# main.net
KiCad netlist of a schematic drawn in EAGLE
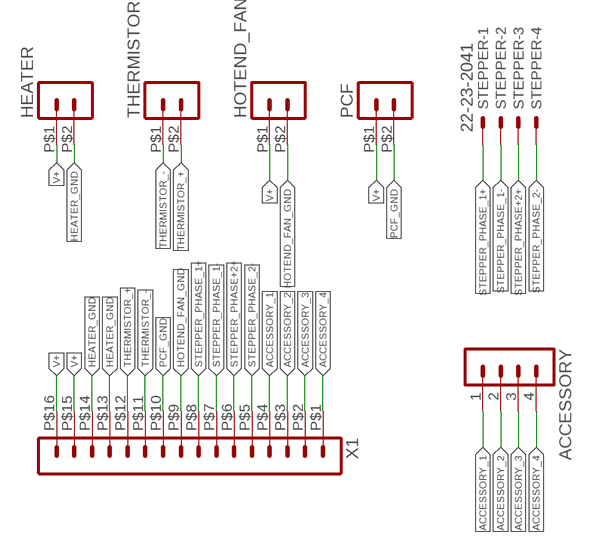
[diagram p0: schematic, sheet 1]

(export (version "E")
  (design (tool "Eeschema 10.0.6"))
  (components
    (comp (ref "ACCESSORY")
      (value "MA04-1")
      (footprint "eagle-import:MA04-1")
      (libsource (lib "eagle-import") (part "MA04-1"))
    )
    (comp (ref "HEATER")
      (value "HEADER_POS2_43650-0224")
      (footprint "eagle-import:43650-0224")
      (libsource (lib "eagle-import") (part "HEADER_POS2_?43650-0224"))
    )
    (comp (ref "HOTEND_FAN")
      (value "HEADER_POS2_43650-0224")
      (footprint "eagle-import:43650-0224")
      (libsource (lib "eagle-import") (part "HEADER_POS2_?43650-0224"))
    )
    (comp (ref "PCF")
      (value "HEADER_POS2_43650-0224")
      (footprint "eagle-import:43650-0224")
      (libsource (lib "eagle-import") (part "HEADER_POS2_?43650-0224"))
    )
    (comp (ref "STEPPER")
      (value "22-23-2041")
      (footprint "eagle-import:22-23-2041")
      (fields (field (name "MF") "MOLEX"))
      (libsource (lib "eagle-import") (part "22-23-2041"))
    )
    (comp (ref "THERMISTOR")
      (value "HEADER_POS2_43650-0224")
      (footprint "eagle-import:43650-0224")
      (libsource (lib "eagle-import") (part "HEADER_POS2_?43650-0224"))
    )
    (comp (ref "X1")
      (value "HEADER_POS16_43045-1618")
      (footprint "eagle-import:43045-1618")
      (libsource (lib "eagle-import") (part "HEADER_POS16_?43045-1618"))
    )
  )
  (nets
    (net (code "1") (name "ACCESSORY_1") (class "Default")
      (node (ref "ACCESSORY") (pin "1") (pinfunction "1_1") (pintype "passive"))
      (node (ref "X1") (pin "P$4") (pinfunction "4_P$4") (pintype "passive"))
    )
    (net (code "2") (name "ACCESSORY_2") (class "Default")
      (node (ref "ACCESSORY") (pin "2") (pinfunction "2_2") (pintype "passive"))
      (node (ref "X1") (pin "P$3") (pinfunction "3_P$3") (pintype "passive"))
    )
    (net (code "3") (name "ACCESSORY_3") (class "Default")
      (node (ref "ACCESSORY") (pin "3") (pinfunction "3_3") (pintype "passive"))
      (node (ref "X1") (pin "P$2") (pinfunction "2_P$2") (pintype "passive"))
    )
    (net (code "4") (name "ACCESSORY_4") (class "Default")
      (node (ref "ACCESSORY") (pin "4") (pinfunction "4_4") (pintype "passive"))
      (node (ref "X1") (pin "P$1") (pinfunction "1_P$1") (pintype "passive"))
    )
    (net (code "5") (name "HEATER_GND") (class "Default")
      (node (ref "HEATER") (pin "P$2") (pinfunction "2_P$2") (pintype "passive"))
      (node (ref "X1") (pin "P$13") (pinfunction "13_P$13") (pintype "passive"))
      (node (ref "X1") (pin "P$14") (pinfunction "14_P$14") (pintype "passive"))
    )
    (net (code "6") (name "HOTEND_FAN_GND") (class "Default")
      (node (ref "HOTEND_FAN") (pin "P$2") (pinfunction "2_P$2") (pintype "passive"))
      (node (ref "X1") (pin "P$9") (pinfunction "9_P$9") (pintype "passive"))
    )
    (net (code "7") (name "PCF_GND") (class "Default")
      (node (ref "PCF") (pin "P$2") (pinfunction "2_P$2") (pintype "passive"))
      (node (ref "X1") (pin "P$10") (pinfunction "10_P$10") (pintype "passive"))
    )
    (net (code "8") (name "STEPPER_PHASE+2+") (class "Default")
      (node (ref "STEPPER") (pin "3") (pinfunction "S_3") (pintype "passive"))
      (node (ref "X1") (pin "P$6") (pinfunction "6_P$6") (pintype "passive"))
    )
    (net (code "9") (name "STEPPER_PHASE_1+") (class "Default")
      (node (ref "STEPPER") (pin "1") (pinfunction "S_1") (pintype "passive"))
      (node (ref "X1") (pin "P$8") (pinfunction "8_P$8") (pintype "passive"))
    )
    (net (code "10") (name "STEPPER_PHASE_1-") (class "Default")
      (node (ref "STEPPER") (pin "2") (pinfunction "S_2") (pintype "passive"))
      (node (ref "X1") (pin "P$7") (pinfunction "7_P$7") (pintype "passive"))
    )
    (net (code "11") (name "STEPPER_PHASE_2-") (class "Default")
      (node (ref "STEPPER") (pin "4") (pinfunction "S_4") (pintype "passive"))
      (node (ref "X1") (pin "P$5") (pinfunction "5_P$5") (pintype "passive"))
    )
    (net (code "12") (name "THERMISTOR_+") (class "Default")
      (node (ref "THERMISTOR") (pin "P$2") (pinfunction "2_P$2") (pintype "passive"))
      (node (ref "X1") (pin "P$12") (pinfunction "12_P$12") (pintype "passive"))
    )
    (net (code "13") (name "THERMISTOR_-") (class "Default")
      (node (ref "THERMISTOR") (pin "P$1") (pinfunction "1_P$1") (pintype "passive"))
      (node (ref "X1") (pin "P$11") (pinfunction "11_P$11") (pintype "passive"))
    )
    (net (code "14") (name "V+") (class "Default")
      (node (ref "HEATER") (pin "P$1") (pinfunction "1_P$1") (pintype "passive"))
      (node (ref "HOTEND_FAN") (pin "P$1") (pinfunction "1_P$1") (pintype "passive"))
      (node (ref "PCF") (pin "P$1") (pinfunction "1_P$1") (pintype "passive"))
      (node (ref "X1") (pin "P$15") (pinfunction "15_P$15") (pintype "passive"))
      (node (ref "X1") (pin "P$16") (pinfunction "16_P$16") (pintype "passive"))
    )
  )
)
